# cb_v2.net
KiCad netlist of a schematic drawn in Altium Designer
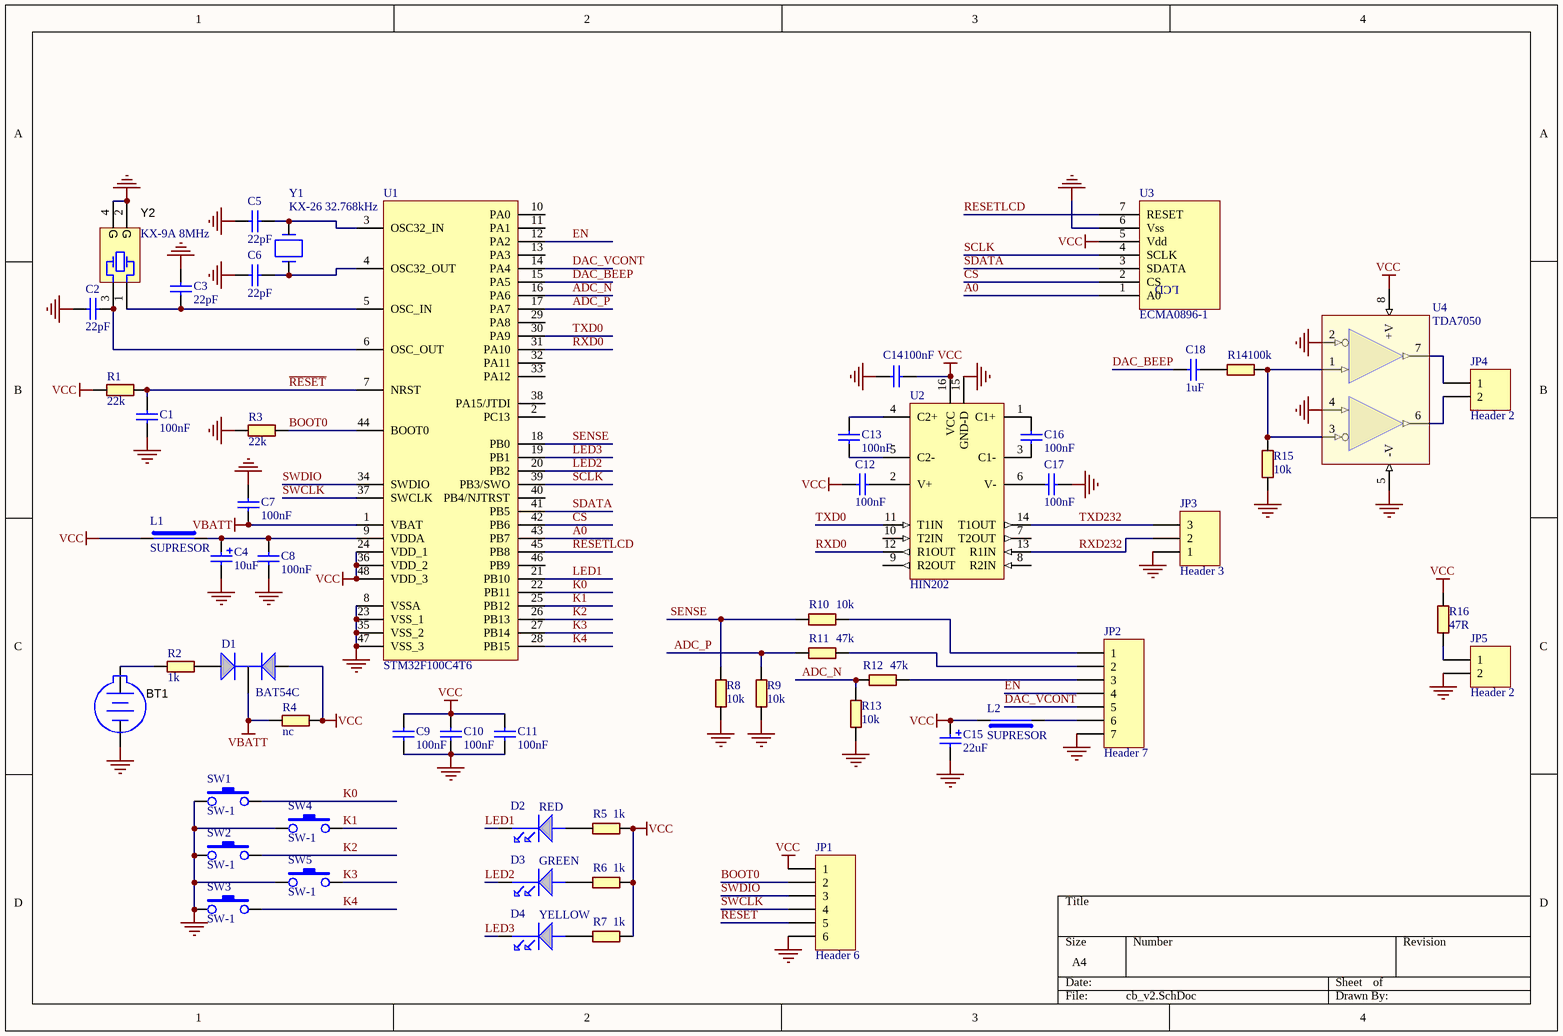
[diagram p0: cb_v2.SchDoc]

(export (version "E")
  (design (tool "Eeschema 10.0.6"))
  (components
    (comp (ref "BT1")
      (value "BS-7")
      (footprint "BAT_BS-7")
      (description "Battery Holder, CR2032, Retainer clip, TH")
      (fields
        (field (name "MANUFACTURER") "Memory Protection Devices")
        (field (name "SYMBOLCREATOR") "a0412235")
        (field (name "PUBLISHER") "Texas Instruments")
      )
      (libsource (lib "ISE4018_TIDA-00374") (part "BS-7"))
    )
    (comp (ref "C1") (value "100nF") (footprint "C-0603") (libsource (lib "RCS-Discret") (part "CAPN")))
    (comp (ref "C2") (value "22pF") (footprint "C-0603") (libsource (lib "RCS-Discret") (part "CAPN")))
    (comp (ref "C3") (value "22pF") (footprint "C-0603") (libsource (lib "RCS-Discret") (part "CAPN")))
    (comp (ref "C4") (value "10uF") (footprint "TANTAL-A") (libsource (lib "RCS-Discret") (part "CAPP")))
    (comp (ref "C5") (value "22pF") (footprint "C-0603") (libsource (lib "RCS-Discret") (part "CAPN")))
    (comp (ref "C6") (value "22pF") (footprint "C-0603") (libsource (lib "RCS-Discret") (part "CAPN")))
    (comp (ref "C7") (value "100nF") (footprint "C-0603") (libsource (lib "RCS-Discret") (part "CAPN")))
    (comp (ref "C8") (value "100nF") (footprint "C-0603") (libsource (lib "RCS-Discret") (part "CAPN")))
    (comp (ref "C9") (value "100nF") (footprint "C-0603") (libsource (lib "RCS-Discret") (part "CAPN")))
    (comp (ref "C10") (value "100nF") (footprint "C-0603") (libsource (lib "RCS-Discret") (part "CAPN")))
    (comp (ref "C11") (value "100nF") (footprint "C-0603") (libsource (lib "RCS-Discret") (part "CAPN")))
    (comp (ref "C12") (value "100nF") (footprint "C-0603") (libsource (lib "RCS-Discret") (part "CAPN")))
    (comp (ref "C13") (value "100nF") (footprint "C-0603") (libsource (lib "RCS-Discret") (part "CAPN")))
    (comp (ref "C14") (value "100nF") (footprint "C-0603") (libsource (lib "RCS-Discret") (part "CAPN")))
    (comp (ref "C15") (value "22uF") (footprint "TANTAL-A") (libsource (lib "RCS-Discret") (part "CAPP")))
    (comp (ref "C16") (value "100nF") (footprint "C-0603") (libsource (lib "RCS-Discret") (part "CAPN")))
    (comp (ref "C17") (value "100nF") (footprint "C-0603") (libsource (lib "RCS-Discret") (part "CAPN")))
    (comp (ref "C18") (value "1uF") (footprint "C-0603") (libsource (lib "RCS-Discret") (part "CAPN")))
    (comp (ref "D1") (value "BAT54C") (footprint "SOT-23") (libsource (lib "RCS-Discret") (part "BAV70")))
    (comp (ref "D2") (value "RED") (footprint "LED-DIP-1") (libsource (lib "RCS-Discret") (part "LED")))
    (comp (ref "D3") (value "GREEN") (footprint "LED-DIP-1") (libsource (lib "RCS-Discret") (part "LED")))
    (comp (ref "D4") (value "YELLOW") (footprint "LED-DIP-1") (libsource (lib "RCS-Discret") (part "LED")))
    (comp (ref "JP1")
      (value "Header 6")
      (footprint "HDR1X6")
      (description "Header, 6-Pin")
      (fields (field (name "PUBLISHER") "Altium Limited"))
      (libsource (lib "Miscellaneous Connectors") (part "Header 6"))
    )
    (comp (ref "JP2")
      (value "Header 7")
      (footprint "HDR1X7")
      (description "Header, 7-Pin")
      (fields (field (name "PUBLISHER") "Altium Limited"))
      (libsource (lib "Miscellaneous Connectors") (part "Header 7"))
    )
    (comp (ref "JP3")
      (value "Header 3")
      (footprint "HDR1X3")
      (description "Header, 3-Pin")
      (fields (field (name "PUBLISHER") "Altium Limited"))
      (libsource (lib "Miscellaneous Connectors") (part "Header 3"))
    )
    (comp (ref "JP4")
      (value "Header 2")
      (footprint "HDR1X2")
      (description "Header, 2-Pin")
      (fields (field (name "PUBLISHER") "Altium Limited"))
      (libsource (lib "Miscellaneous Connectors") (part "Header 2"))
    )
    (comp (ref "JP5")
      (value "Header 2")
      (footprint "HDR1X2")
      (description "Header, 2-Pin")
      (fields (field (name "PUBLISHER") "Altium Limited"))
      (libsource (lib "Miscellaneous Connectors") (part "Header 2"))
    )
    (comp (ref "L1")
      (value "SUPRESOR")
      (footprint "R-1206")
      (libsource (lib "RCS-Discret") (part "SUPRESOR"))
    )
    (comp (ref "L2")
      (value "SUPRESOR")
      (footprint "R-1206")
      (libsource (lib "RCS-Discret") (part "SUPRESOR"))
    )
    (comp (ref "R1") (value "22k") (footprint "R-0603") (libsource (lib "RCS-Discret") (part "RES")))
    (comp (ref "R2") (value "1k") (footprint "R-0603") (libsource (lib "RCS-Discret") (part "RES")))
    (comp (ref "R3") (value "22k") (footprint "R-0603") (libsource (lib "RCS-Discret") (part "RES")))
    (comp (ref "R4") (value "nc") (footprint "R-0603") (libsource (lib "RCS-Discret") (part "RES")))
    (comp (ref "R5") (value "1k") (footprint "R-0603") (libsource (lib "RCS-Discret") (part "RES")))
    (comp (ref "R6") (value "1k") (footprint "R-0603") (libsource (lib "RCS-Discret") (part "RES")))
    (comp (ref "R7") (value "1k") (footprint "R-0603") (libsource (lib "RCS-Discret") (part "RES")))
    (comp (ref "R8") (value "10k") (footprint "R-0603") (libsource (lib "") (part "RES_2")))
    (comp (ref "R9") (value "10k") (footprint "R-0603") (libsource (lib "") (part "RES_2")))
    (comp (ref "R10") (value "10k") (footprint "R-0603") (libsource (lib "RCS-Discret") (part "RES")))
    (comp (ref "R11") (value "47k") (footprint "R-0603") (libsource (lib "RCS-Discret") (part "RES")))
    (comp (ref "R12") (value "47k") (footprint "R-0603") (libsource (lib "") (part "RES_1")))
    (comp (ref "R13") (value "10k") (footprint "R-0603") (libsource (lib "") (part "RES_2")))
    (comp (ref "R14") (value "100k") (footprint "R-0603") (libsource (lib "RCS-Discret") (part "RES")))
    (comp (ref "R15") (value "10k") (footprint "R-0603") (libsource (lib "") (part "RES_2")))
    (comp (ref "R16") (value "47R") (footprint "R-1206") (libsource (lib "") (part "RES_2")))
    (comp (ref "SW1") (value "SW-1") (footprint "SW4-2") (libsource (lib "RCS-Connect&pushe") (part "SW-1")))
    (comp (ref "SW2") (value "SW-1") (footprint "SW4-2") (libsource (lib "RCS-Connect&pushe") (part "SW-1")))
    (comp (ref "SW3") (value "SW-1") (footprint "SW4-2") (libsource (lib "RCS-Connect&pushe") (part "SW-1")))
    (comp (ref "SW4") (value "SW-1") (footprint "SW4-2") (libsource (lib "RCS-Connect&pushe") (part "SW-1")))
    (comp (ref "SW5") (value "SW-1") (footprint "SW4-2") (libsource (lib "RCS-Connect&pushe") (part "SW-1")))
    (comp (ref "U1")
      (value "STM32F100C4T6")
      (footprint "TSQFP50P900X900X160-48N")
      (libsource (lib "cb_v0") (part "STM32F100CxT6"))
    )
    (comp (ref "U2")
      (value "HIN202")
      (footprint "SSOP16NW")
      (description "RS232 driver")
      (libsource (lib "RCS-IMS") (part "HIN202"))
    )
    (comp (ref "U3")
      (value "ECMA0896-1")
      (footprint "ECMA0896")
      (libsource (lib "RCS-IMS") (part "ECMA0896"))
    )
    (comp (ref "U4")
      (value "TDA7050")
      (footprint "SO8-(SOT-96-1)")
      (libsource (lib "cb_v2") (part "TDA7050"))
    )
    (comp (ref "Y1")
      (value "KX-26 32.768kHz")
      (footprint "KX-327")
      (libsource (lib "RCS-Discret") (part "Y"))
    )
    (comp (ref "Y2")
      (value "KX-9A 8MHz")
      (footprint "KX-9A")
      (description "Crystal, 24 MHz, 9 pF, SMD")
      (fields
        (field (name "PARTNUMBER") "TSX-3225 24.0000MF20G-AC3")
        (field (name "MANUFACTURER") "Epson")
        (field (name "SYMBOLCREATOR") "a0412235")
        (field (name "PUBLISHER") "Texas Instruments")
      )
      (libsource (lib "ISE4018_TIDA-00374") (part "TSX-3225 24.0000MF20G-AC3"))
    )
  )
  (nets
    (net (code "1") (name "/A0") (class "Default")
      (node (ref "U1") (pin "43") (pinfunction "PB7_43") (pintype "passive"))
      (node (ref "U3") (pin "1") (pinfunction "A0_1") (pintype "passive"))
    )
    (net (code "2") (name "/ADC_N") (class "Default")
      (node (ref "R12") (pin "2") (pinfunction "2_2") (pintype "passive"))
      (node (ref "R13") (pin "2") (pinfunction "2_2") (pintype "passive"))
      (node (ref "U1") (pin "16") (pinfunction "PA6_16") (pintype "passive"))
    )
    (net (code "3") (name "/ADC_P") (class "Default")
      (node (ref "R11") (pin "1") (pinfunction "1_1") (pintype "passive"))
      (node (ref "R9") (pin "2") (pinfunction "2_2") (pintype "passive"))
      (node (ref "U1") (pin "17") (pinfunction "PA7_17") (pintype "passive"))
    )
    (net (code "4") (name "/BOOT0") (class "Default")
      (node (ref "JP1") (pin "2") (pinfunction "2_2") (pintype "passive"))
      (node (ref "R3") (pin "2") (pinfunction "2_2") (pintype "passive"))
      (node (ref "U1") (pin "44") (pinfunction "BOOT0_44") (pintype "passive"))
    )
    (net (code "5") (name "/CS") (class "Default")
      (node (ref "U1") (pin "42") (pinfunction "PB6_42") (pintype "passive"))
      (node (ref "U3") (pin "2") (pinfunction "CS_2") (pintype "passive"))
    )
    (net (code "6") (name "/DAC_BEEP") (class "Default")
      (node (ref "C18") (pin "1") (pinfunction "1_1") (pintype "passive"))
      (node (ref "U1") (pin "15") (pinfunction "PA5_15") (pintype "passive"))
    )
    (net (code "7") (name "/DAC_VCONT") (class "Default")
      (node (ref "JP2") (pin "5") (pinfunction "5_5") (pintype "passive"))
      (node (ref "U1") (pin "14") (pinfunction "PA4_14") (pintype "passive"))
    )
    (net (code "8") (name "/EN") (class "Default")
      (node (ref "JP2") (pin "4") (pinfunction "4_4") (pintype "passive"))
      (node (ref "U1") (pin "12") (pinfunction "PA2_12") (pintype "passive"))
    )
    (net (code "9") (name "/K0") (class "Default")
      (node (ref "SW1") (pin "1") (pinfunction "1_1") (pintype "passive"))
      (node (ref "U1") (pin "22") (pinfunction "PB11_22") (pintype "passive"))
    )
    (net (code "10") (name "/K1") (class "Default")
      (node (ref "SW4") (pin "1") (pinfunction "1_1") (pintype "passive"))
      (node (ref "U1") (pin "25") (pinfunction "PB12_25") (pintype "passive"))
    )
    (net (code "11") (name "/K2") (class "Default")
      (node (ref "SW2") (pin "1") (pinfunction "1_1") (pintype "passive"))
      (node (ref "U1") (pin "26") (pinfunction "PB13_26") (pintype "passive"))
    )
    (net (code "12") (name "/K3") (class "Default")
      (node (ref "SW5") (pin "1") (pinfunction "1_1") (pintype "passive"))
      (node (ref "U1") (pin "27") (pinfunction "PB14_27") (pintype "passive"))
    )
    (net (code "13") (name "/K4") (class "Default")
      (node (ref "SW3") (pin "1") (pinfunction "1_1") (pintype "passive"))
      (node (ref "U1") (pin "28") (pinfunction "PB15_28") (pintype "passive"))
    )
    (net (code "14") (name "/LED1") (class "Default")
      (node (ref "D2") (pin "K") (pinfunction "CATHODE_K") (pintype "passive"))
      (node (ref "U1") (pin "21") (pinfunction "PB10_21") (pintype "passive"))
    )
    (net (code "15") (name "/LED2") (class "Default")
      (node (ref "D3") (pin "K") (pinfunction "CATHODE_K") (pintype "passive"))
      (node (ref "U1") (pin "20") (pinfunction "PB2_20") (pintype "passive"))
    )
    (net (code "16") (name "/LED3") (class "Default")
      (node (ref "D4") (pin "K") (pinfunction "CATHODE_K") (pintype "passive"))
      (node (ref "U1") (pin "19") (pinfunction "PB1_19") (pintype "passive"))
    )
    (net (code "17") (name "/RESETLCD") (class "Default")
      (node (ref "U1") (pin "45") (pinfunction "PB8_45") (pintype "passive"))
      (node (ref "U3") (pin "7") (pinfunction "RESET_7") (pintype "passive"))
    )
    (net (code "18") (name "/RXD0") (class "Default")
      (node (ref "U1") (pin "31") (pinfunction "PA10_31") (pintype "passive"))
      (node (ref "U2") (pin "12") (pinfunction "R1OUT_12") (pintype "output"))
    )
    (net (code "19") (name "/RXD232") (class "Default")
      (node (ref "JP3") (pin "2") (pinfunction "2_2") (pintype "passive"))
      (node (ref "U2") (pin "13") (pinfunction "R1IN_13") (pintype "input"))
    )
    (net (code "20") (name "/SCLK") (class "Default")
      (node (ref "U1") (pin "39") (pinfunction "PB3/SWO_39") (pintype "passive"))
      (node (ref "U3") (pin "4") (pinfunction "SCLK_4") (pintype "passive"))
    )
    (net (code "21") (name "/SDATA") (class "Default")
      (node (ref "U1") (pin "41") (pinfunction "PB5_41") (pintype "passive"))
      (node (ref "U3") (pin "3") (pinfunction "SDATA_3") (pintype "passive"))
    )
    (net (code "22") (name "/SENSE") (class "Default")
      (node (ref "R10") (pin "1") (pinfunction "1_1") (pintype "passive"))
      (node (ref "R8") (pin "2") (pinfunction "2_2") (pintype "passive"))
      (node (ref "U1") (pin "18") (pinfunction "PB0_18") (pintype "passive"))
    )
    (net (code "23") (name "/SWCLK") (class "Default")
      (node (ref "JP1") (pin "4") (pinfunction "4_4") (pintype "passive"))
      (node (ref "U1") (pin "37") (pinfunction "SWCLK_37") (pintype "passive"))
    )
    (net (code "24") (name "/SWDIO") (class "Default")
      (node (ref "JP1") (pin "3") (pinfunction "3_3") (pintype "passive"))
      (node (ref "U1") (pin "34") (pinfunction "SWDIO_34") (pintype "passive"))
    )
    (net (code "25") (name "/TXD0") (class "Default")
      (node (ref "U1") (pin "30") (pinfunction "PA9_30") (pintype "passive"))
      (node (ref "U2") (pin "11") (pinfunction "T1IN_11") (pintype "input"))
    )
    (net (code "26") (name "/TXD232") (class "Default")
      (node (ref "JP3") (pin "3") (pinfunction "3_3") (pintype "passive"))
      (node (ref "U2") (pin "14") (pinfunction "T1OUT_14") (pintype "output"))
    )
    (net (code "27") (name "/~{RESET}") (class "Default")
      (node (ref "C1") (pin "1") (pinfunction "1_1") (pintype "passive"))
      (node (ref "JP1") (pin "5") (pinfunction "5_5") (pintype "passive"))
      (node (ref "R1") (pin "2") (pinfunction "2_2") (pintype "passive"))
      (node (ref "U1") (pin "7") (pinfunction "NRST_7") (pintype "passive"))
    )
    (net (code "28") (name "GND") (class "Default")
      (node (ref "BT1") (pin "2") (pinfunction "-_2") (pintype "passive"))
      (node (ref "C1") (pin "2") (pinfunction "2_2") (pintype "passive"))
      (node (ref "C10") (pin "2") (pinfunction "2_2") (pintype "passive"))
      (node (ref "C11") (pin "2") (pinfunction "2_2") (pintype "passive"))
      (node (ref "C14") (pin "1") (pinfunction "1_1") (pintype "passive"))
      (node (ref "C15") (pin "1") (pinfunction "1_1") (pintype "passive"))
      (node (ref "C17") (pin "2") (pinfunction "2_2") (pintype "passive"))
      (node (ref "C2") (pin "1") (pinfunction "1_1") (pintype "passive"))
      (node (ref "C3") (pin "2") (pinfunction "2_2") (pintype "passive"))
      (node (ref "C4") (pin "1") (pinfunction "1_1") (pintype "passive"))
      (node (ref "C5") (pin "1") (pinfunction "1_1") (pintype "passive"))
      (node (ref "C6") (pin "2") (pinfunction "2_2") (pintype "passive"))
      (node (ref "C7") (pin "1") (pinfunction "1_1") (pintype "passive"))
      (node (ref "C8") (pin "2") (pinfunction "2_2") (pintype "passive"))
      (node (ref "C9") (pin "2") (pinfunction "2_2") (pintype "passive"))
      (node (ref "JP1") (pin "6") (pinfunction "6_6") (pintype "passive"))
      (node (ref "JP2") (pin "7") (pinfunction "7_7") (pintype "passive"))
      (node (ref "JP3") (pin "1") (pinfunction "1_1") (pintype "passive"))
      (node (ref "JP5") (pin "2") (pinfunction "2_2") (pintype "passive"))
      (node (ref "R13") (pin "1") (pinfunction "1_1") (pintype "passive"))
      (node (ref "R15") (pin "1") (pinfunction "1_1") (pintype "passive"))
      (node (ref "R3") (pin "1") (pinfunction "1_1") (pintype "passive"))
      (node (ref "R8") (pin "1") (pinfunction "1_1") (pintype "passive"))
      (node (ref "R9") (pin "1") (pinfunction "1_1") (pintype "passive"))
      (node (ref "SW1") (pin "2") (pinfunction "2_2") (pintype "passive"))
      (node (ref "SW2") (pin "2") (pinfunction "2_2") (pintype "passive"))
      (node (ref "SW3") (pin "2") (pinfunction "2_2") (pintype "passive"))
      (node (ref "SW4") (pin "2") (pinfunction "2_2") (pintype "passive"))
      (node (ref "SW5") (pin "2") (pinfunction "2_2") (pintype "passive"))
      (node (ref "U1") (pin "23") (pinfunction "VSS_1_23") (pintype "passive"))
      (node (ref "U1") (pin "35") (pinfunction "VSS_2_35") (pintype "passive"))
      (node (ref "U1") (pin "47") (pinfunction "VSS_3_47") (pintype "passive"))
      (node (ref "U1") (pin "8") (pinfunction "VSSA_8") (pintype "passive"))
      (node (ref "U2") (pin "15") (pinfunction "GND-D_15") (pintype "power_in"))
      (node (ref "U3") (pin "6") (pinfunction "Vss_6") (pintype "passive"))
      (node (ref "U4") (pin "2") (pinfunction "IN1-_2") (pintype "input"))
      (node (ref "U4") (pin "4") (pinfunction "IN2+_4") (pintype "input"))
      (node (ref "U4") (pin "5") (pinfunction "-V_5") (pintype "input"))
      (node (ref "Y2") (pin "2") (pinfunction "GND_2") (pintype "power_in"))
      (node (ref "Y2") (pin "4") (pinfunction "GND_4") (pintype "power_in"))
    )
    (net (code "29") (name "Net-(BT1-+)") (class "Default")
      (node (ref "BT1") (pin "1") (pinfunction "+_1") (pintype "passive"))
      (node (ref "R2") (pin "1") (pinfunction "1_1") (pintype "passive"))
    )
    (net (code "30") (name "Net-(C18-Pad2)") (class "Default")
      (node (ref "C18") (pin "2") (pinfunction "2_2") (pintype "passive"))
      (node (ref "R14") (pin "1") (pinfunction "1_1") (pintype "passive"))
    )
    (net (code "31") (name "Net-(D1-Pad3)") (class "Default")
      (node (ref "D1") (pin "3") (pinfunction "3_3") (pintype "passive"))
      (node (ref "R2") (pin "2") (pinfunction "2_2") (pintype "passive"))
    )
    (net (code "32") (name "Net-(D2-ANODE)") (class "Default")
      (node (ref "D2") (pin "A") (pinfunction "ANODE_A") (pintype "passive"))
      (node (ref "R5") (pin "1") (pinfunction "1_1") (pintype "passive"))
    )
    (net (code "33") (name "Net-(D3-ANODE)") (class "Default")
      (node (ref "D3") (pin "A") (pinfunction "ANODE_A") (pintype "passive"))
      (node (ref "R6") (pin "1") (pinfunction "1_1") (pintype "passive"))
    )
    (net (code "34") (name "Net-(D4-ANODE)") (class "Default")
      (node (ref "D4") (pin "A") (pinfunction "ANODE_A") (pintype "passive"))
      (node (ref "R7") (pin "1") (pinfunction "1_1") (pintype "passive"))
    )
    (net (code "35") (name "Net-(JP2-Pad1)") (class "Default")
      (node (ref "JP2") (pin "1") (pinfunction "1_1") (pintype "passive"))
      (node (ref "R10") (pin "2") (pinfunction "2_2") (pintype "passive"))
    )
    (net (code "36") (name "Net-(JP2-Pad2)") (class "Default")
      (node (ref "JP2") (pin "2") (pinfunction "2_2") (pintype "passive"))
      (node (ref "R11") (pin "2") (pinfunction "2_2") (pintype "passive"))
    )
    (net (code "37") (name "Net-(JP2-Pad3)") (class "Default")
      (node (ref "JP2") (pin "3") (pinfunction "3_3") (pintype "passive"))
      (node (ref "R12") (pin "1") (pinfunction "1_1") (pintype "passive"))
    )
    (net (code "38") (name "Net-(JP2-Pad6)") (class "Default")
      (node (ref "JP2") (pin "6") (pinfunction "6_6") (pintype "passive"))
      (node (ref "L2") (pin "1") (pinfunction "1_1") (pintype "passive"))
    )
    (net (code "39") (name "Net-(JP5-Pad1)") (class "Default")
      (node (ref "JP5") (pin "1") (pinfunction "1_1") (pintype "passive"))
      (node (ref "R16") (pin "1") (pinfunction "1_1") (pintype "passive"))
    )
    (net (code "40") (name "Net-(U1-OSC32_IN)") (class "Default")
      (node (ref "C5") (pin "2") (pinfunction "2_2") (pintype "passive"))
      (node (ref "U1") (pin "3") (pinfunction "OSC32_IN_3") (pintype "passive"))
      (node (ref "Y1") (pin "1") (pinfunction "1_1") (pintype "passive"))
    )
    (net (code "41") (name "Net-(U1-OSC32_OUT)") (class "Default")
      (node (ref "C6") (pin "1") (pinfunction "1_1") (pintype "passive"))
      (node (ref "U1") (pin "4") (pinfunction "OSC32_OUT_4") (pintype "passive"))
      (node (ref "Y1") (pin "2") (pinfunction "2_2") (pintype "passive"))
    )
    (net (code "42") (name "Net-(U1-OSC_IN)") (class "Default")
      (node (ref "C3") (pin "1") (pinfunction "1_1") (pintype "passive"))
      (node (ref "U1") (pin "5") (pinfunction "OSC_IN_5") (pintype "passive"))
      (node (ref "Y2") (pin "1") (pinfunction "1_1") (pintype "passive"))
    )
    (net (code "43") (name "Net-(U1-OSC_OUT)") (class "Default")
      (node (ref "C2") (pin "2") (pinfunction "2_2") (pintype "passive"))
      (node (ref "U1") (pin "6") (pinfunction "OSC_OUT_6") (pintype "passive"))
      (node (ref "Y2") (pin "3") (pinfunction "3_3") (pintype "passive"))
    )
    (net (code "44") (name "Net-(U1-VDDA)") (class "Default")
      (node (ref "C4") (pin "2") (pinfunction "2_2") (pintype "passive"))
      (node (ref "C8") (pin "1") (pinfunction "1_1") (pintype "passive"))
      (node (ref "L1") (pin "2") (pinfunction "2_2") (pintype "passive"))
      (node (ref "U1") (pin "9") (pinfunction "VDDA_9") (pintype "passive"))
    )
    (net (code "45") (name "Net-(U2-C1+)") (class "Default")
      (node (ref "C16") (pin "1") (pinfunction "1_1") (pintype "passive"))
      (node (ref "U2") (pin "1") (pinfunction "C1+_1") (pintype "passive"))
    )
    (net (code "46") (name "Net-(U2-C1-)") (class "Default")
      (node (ref "C16") (pin "2") (pinfunction "2_2") (pintype "passive"))
      (node (ref "U2") (pin "3") (pinfunction "C1-_3") (pintype "passive"))
    )
    (net (code "47") (name "Net-(U2-C2+)") (class "Default")
      (node (ref "C13") (pin "1") (pinfunction "1_1") (pintype "passive"))
      (node (ref "U2") (pin "4") (pinfunction "C2+_4") (pintype "passive"))
    )
    (net (code "48") (name "Net-(U2-C2-)") (class "Default")
      (node (ref "C13") (pin "2") (pinfunction "2_2") (pintype "passive"))
      (node (ref "U2") (pin "5") (pinfunction "C2-_5") (pintype "passive"))
    )
    (net (code "49") (name "Net-(U2-V+)") (class "Default")
      (node (ref "C12") (pin "2") (pinfunction "2_2") (pintype "passive"))
      (node (ref "U2") (pin "2") (pinfunction "V+_2") (pintype "passive"))
    )
    (net (code "50") (name "Net-(U2-V-)") (class "Default")
      (node (ref "C17") (pin "1") (pinfunction "1_1") (pintype "passive"))
      (node (ref "U2") (pin "6") (pinfunction "V-_6") (pintype "passive"))
    )
    (net (code "51") (name "Net-(U4-IN1+)") (class "Default")
      (node (ref "R14") (pin "2") (pinfunction "2_2") (pintype "passive"))
      (node (ref "R15") (pin "2") (pinfunction "2_2") (pintype "passive"))
      (node (ref "U4") (pin "1") (pinfunction "IN1+_1") (pintype "input"))
      (node (ref "U4") (pin "3") (pinfunction "IN2-_3") (pintype "input"))
    )
    (net (code "52") (name "Net-(U4-OUT1)") (class "Default")
      (node (ref "JP4") (pin "1") (pinfunction "1_1") (pintype "passive"))
      (node (ref "U4") (pin "7") (pinfunction "OUT1_7") (pintype "output"))
    )
    (net (code "53") (name "Net-(U4-OUT2)") (class "Default")
      (node (ref "JP4") (pin "2") (pinfunction "2_2") (pintype "passive"))
      (node (ref "U4") (pin "6") (pinfunction "OUT2_6") (pintype "output"))
    )
    (net (code "54") (name "VBATT") (class "Default")
      (node (ref "C7") (pin "2") (pinfunction "2_2") (pintype "passive"))
      (node (ref "D1") (pin "2") (pinfunction "2_2") (pintype "passive"))
      (node (ref "R4") (pin "1") (pinfunction "1_1") (pintype "passive"))
      (node (ref "U1") (pin "1") (pinfunction "VBAT_1") (pintype "passive"))
    )
    (net (code "55") (name "VCC") (class "Default")
      (node (ref "C10") (pin "1") (pinfunction "1_1") (pintype "passive"))
      (node (ref "C11") (pin "1") (pinfunction "1_1") (pintype "passive"))
      (node (ref "C12") (pin "1") (pinfunction "1_1") (pintype "passive"))
      (node (ref "C14") (pin "2") (pinfunction "2_2") (pintype "passive"))
      (node (ref "C15") (pin "2") (pinfunction "2_2") (pintype "passive"))
      (node (ref "C9") (pin "1") (pinfunction "1_1") (pintype "passive"))
      (node (ref "D1") (pin "1") (pinfunction "1_1") (pintype "passive"))
      (node (ref "JP1") (pin "1") (pinfunction "1_1") (pintype "passive"))
      (node (ref "L1") (pin "1") (pinfunction "1_1") (pintype "passive"))
      (node (ref "L2") (pin "2") (pinfunction "2_2") (pintype "passive"))
      (node (ref "R1") (pin "1") (pinfunction "1_1") (pintype "passive"))
      (node (ref "R16") (pin "2") (pinfunction "2_2") (pintype "passive"))
      (node (ref "R4") (pin "2") (pinfunction "2_2") (pintype "passive"))
      (node (ref "R5") (pin "2") (pinfunction "2_2") (pintype "passive"))
      (node (ref "R6") (pin "2") (pinfunction "2_2") (pintype "passive"))
      (node (ref "R7") (pin "2") (pinfunction "2_2") (pintype "passive"))
      (node (ref "U1") (pin "24") (pinfunction "VDD_1_24") (pintype "passive"))
      (node (ref "U1") (pin "36") (pinfunction "VDD_2_36") (pintype "passive"))
      (node (ref "U1") (pin "48") (pinfunction "VDD_3_48") (pintype "passive"))
      (node (ref "U2") (pin "16") (pinfunction "VCC_16") (pintype "power_in"))
      (node (ref "U3") (pin "5") (pinfunction "Vdd_5") (pintype "passive"))
      (node (ref "U4") (pin "8") (pinfunction "+V_8") (pintype "input"))
    )
    (net (code "56") (name "unconnected-(U1-PA0-Pad10)") (class "Default")
      (node (ref "U1") (pin "10") (pinfunction "PA0_10") (pintype "passive"))
    )
    (net (code "57") (name "unconnected-(U1-PA1-Pad11)") (class "Default")
      (node (ref "U1") (pin "11") (pinfunction "PA1_11") (pintype "passive"))
    )
    (net (code "58") (name "unconnected-(U1-PA3-Pad13)") (class "Default")
      (node (ref "U1") (pin "13") (pinfunction "PA3_13") (pintype "passive"))
    )
    (net (code "59") (name "unconnected-(U1-PA8-Pad29)") (class "Default")
      (node (ref "U1") (pin "29") (pinfunction "PA8_29") (pintype "passive"))
    )
    (net (code "60") (name "unconnected-(U1-PA11-Pad32)") (class "Default")
      (node (ref "U1") (pin "32") (pinfunction "PA11_32") (pintype "passive"))
    )
    (net (code "61") (name "unconnected-(U1-PA12-Pad33)") (class "Default")
      (node (ref "U1") (pin "33") (pinfunction "PA12_33") (pintype "passive"))
    )
    (net (code "62") (name "unconnected-(U1-PA15{slash}JTDI-Pad38)") (class "Default")
      (node (ref "U1") (pin "38") (pinfunction "PA15/JTDI_38") (pintype "passive"))
    )
    (net (code "63") (name "unconnected-(U1-PB4{slash}NJTRST-Pad40)") (class "Default")
      (node (ref "U1") (pin "40") (pinfunction "PB4/NJTRST_40") (pintype "passive"))
    )
    (net (code "64") (name "unconnected-(U1-PB9-Pad46)") (class "Default")
      (node (ref "U1") (pin "46") (pinfunction "PB9_46") (pintype "passive"))
    )
    (net (code "65") (name "unconnected-(U1-PC13-Pad2)") (class "Default")
      (node (ref "U1") (pin "2") (pinfunction "PC13_2") (pintype "passive"))
    )
    (net (code "66") (name "unconnected-(U2-R2IN-Pad8)") (class "Default")
      (node (ref "U2") (pin "8") (pinfunction "R2IN_8") (pintype "input"))
    )
    (net (code "67") (name "unconnected-(U2-R2OUT-Pad9)") (class "Default")
      (node (ref "U2") (pin "9") (pinfunction "R2OUT_9") (pintype "output"))
    )
    (net (code "68") (name "unconnected-(U2-T2IN-Pad10)") (class "Default")
      (node (ref "U2") (pin "10") (pinfunction "T2IN_10") (pintype "input"))
    )
    (net (code "69") (name "unconnected-(U2-T2OUT-Pad7)") (class "Default")
      (node (ref "U2") (pin "7") (pinfunction "T2OUT_7") (pintype "output"))
    )
  )
)
